# z0-probe-v7.net
KiCad netlist of a schematic drawn in EAGLE
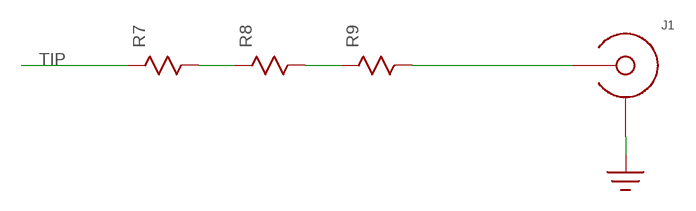
[diagram p0: schematic, sheet 1]

(export (version "E")
  (design (tool "Eeschema 10.0.6"))
  (components
    (comp (ref "J1")
      (value "SMA-EDGE-LAUNCH")
      (footprint "eagle-import:SMA_EDGE_LAUNCH_2L_4020_TAPER_FIXED")
      (libsource (lib "eagle-import") (part "SMA-EDGE-LAUNCH"))
    )
    (comp (ref "R7")
      (value "R0603-TIGHT")
      (footprint "eagle-import:0603_TIGHT")
      (libsource (lib "eagle-import") (part "R0603-TIGHT"))
    )
    (comp (ref "R8")
      (value "R0603-TIGHT")
      (footprint "eagle-import:0603_TIGHT")
      (libsource (lib "eagle-import") (part "R0603-TIGHT"))
    )
    (comp (ref "R9")
      (value "R0603-TIGHT")
      (footprint "eagle-import:0603_TIGHT")
      (libsource (lib "eagle-import") (part "R0603-TIGHT"))
    )
  )
  (nets
    (net (code "1") (name "/TIP") (class "Default")
      (node (ref "R7") (pin "P$1") (pinfunction "P$3_P$1") (pintype "bidirectional"))
    )
    (net (code "2") (name "GND") (class "Default")
      (node (ref "J1") (pin "BOTTOM_GND") (pinfunction "SHIELD_BOTTOM_GND") (pintype "bidirectional"))
      (node (ref "J1") (pin "GND@1") (pinfunction "SHIELD_GND@1") (pintype "bidirectional"))
      (node (ref "J1") (pin "GND@14") (pinfunction "SHIELD_GND@14") (pintype "bidirectional"))
      (node (ref "J1") (pin "GND@15") (pinfunction "SHIELD_GND@15") (pintype "bidirectional"))
      (node (ref "J1") (pin "GND@16") (pinfunction "SHIELD_GND@16") (pintype "bidirectional"))
      (node (ref "J1") (pin "GND@17") (pinfunction "SHIELD_GND@17") (pintype "bidirectional"))
      (node (ref "J1") (pin "GND@2") (pinfunction "SHIELD_GND@2") (pintype "bidirectional"))
      (node (ref "J1") (pin "GND@3") (pinfunction "SHIELD_GND@3") (pintype "bidirectional"))
      (node (ref "J1") (pin "GND@4") (pinfunction "SHIELD_GND@4") (pintype "bidirectional"))
      (node (ref "J1") (pin "GND@5") (pinfunction "SHIELD_GND@5") (pintype "bidirectional"))
      (node (ref "J1") (pin "GND@6") (pinfunction "SHIELD_GND@6") (pintype "bidirectional"))
      (node (ref "J1") (pin "GND@7") (pinfunction "SHIELD_GND@7") (pintype "bidirectional"))
      (node (ref "J1") (pin "GND@8") (pinfunction "SHIELD_GND@8") (pintype "bidirectional"))
      (node (ref "J1") (pin "GND_PAD1") (pinfunction "SHIELD_GND_PAD1") (pintype "bidirectional"))
      (node (ref "J1") (pin "GND_PAD2") (pinfunction "SHIELD_GND_PAD2") (pintype "bidirectional"))
      (node (ref "J1") (pin "P$1") (pinfunction "SHIELD_P$1") (pintype "bidirectional"))
      (node (ref "J1") (pin "P$2") (pinfunction "SHIELD_P$2") (pintype "bidirectional"))
    )
    (net (code "3") (name "Net-(R7-P$4)") (class "Default")
      (node (ref "R7") (pin "P$2") (pinfunction "P$4_P$2") (pintype "bidirectional"))
      (node (ref "R8") (pin "P$1") (pinfunction "P$3_P$1") (pintype "bidirectional"))
    )
    (net (code "4") (name "Net-(R8-P$4)") (class "Default")
      (node (ref "R8") (pin "P$2") (pinfunction "P$4_P$2") (pintype "bidirectional"))
      (node (ref "R9") (pin "P$1") (pinfunction "P$3_P$1") (pintype "bidirectional"))
    )
    (net (code "5") (name "Net-(R9-P$4)") (class "Default")
      (node (ref "J1") (pin "CENTER@1") (pinfunction "CENTER_CENTER@1") (pintype "bidirectional"))
      (node (ref "J1") (pin "P$3") (pinfunction "CENTER_P$3") (pintype "bidirectional"))
      (node (ref "R9") (pin "P$2") (pinfunction "P$4_P$2") (pintype "bidirectional"))
    )
  )
)
